# main.net
KiCad netlist of a schematic drawn in Altium Designer
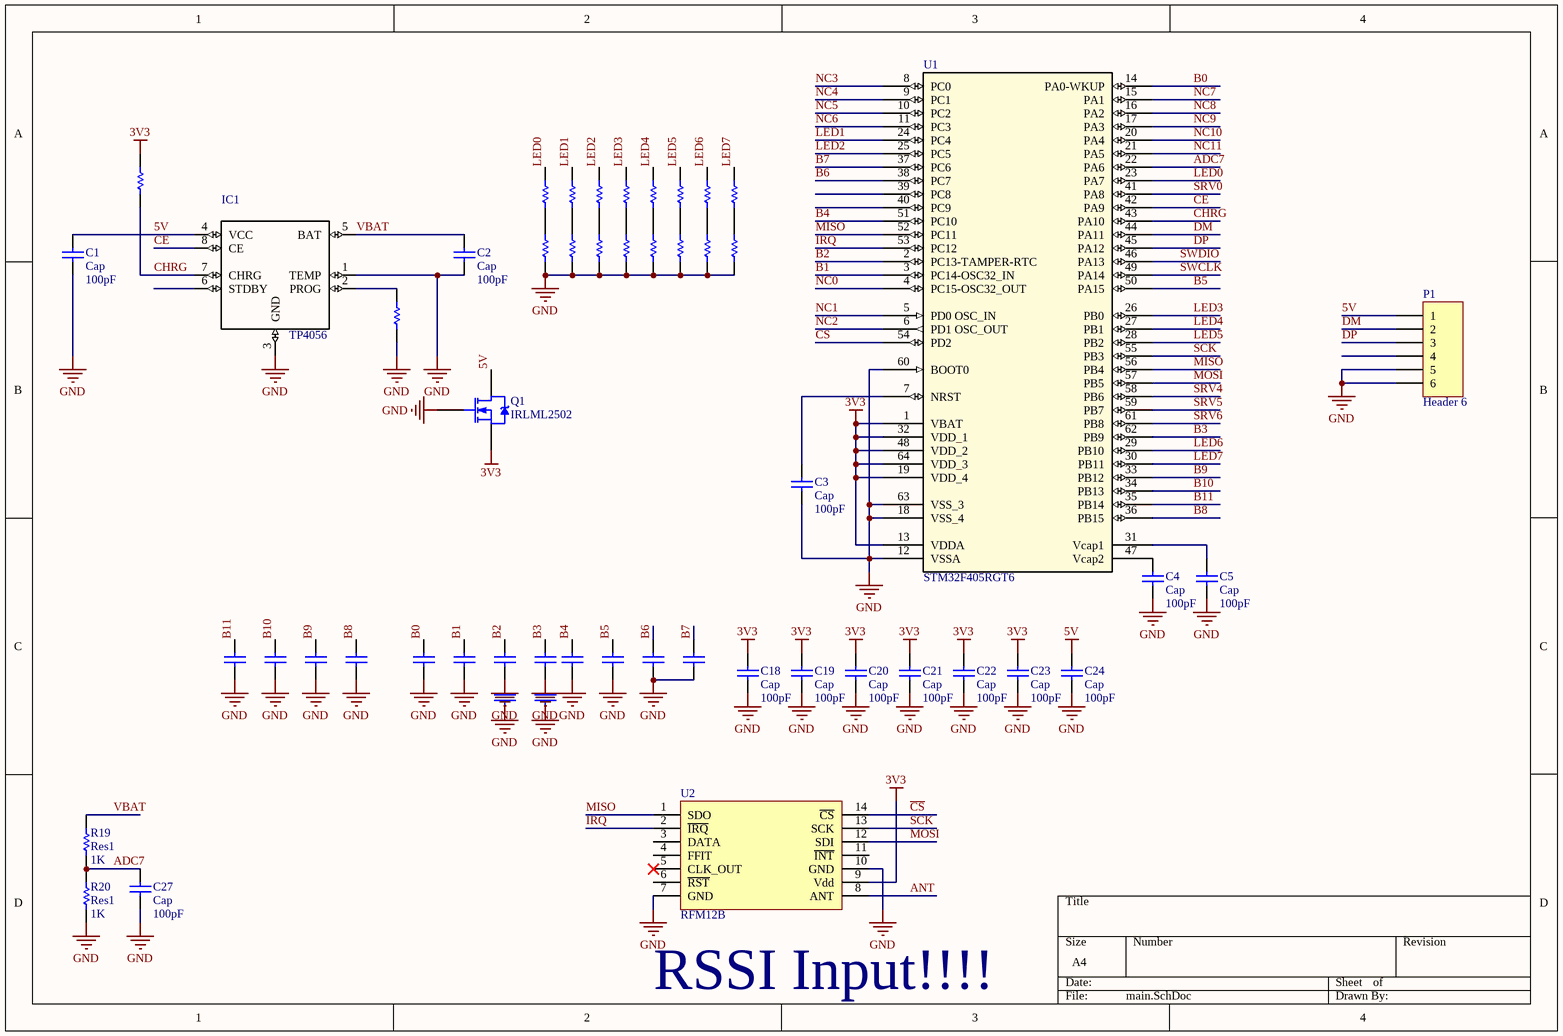
[diagram p0: main.SchDoc]

(export (version "E")
  (design (tool "Eeschema 10.0.6"))
  (components
    (comp (ref "C1")
      (value "Cap")
      (footprint "RC_1210_T1.8")
      (description "Capacitor")
      (fields (field (name "ALTIUM_VALUE") "100pF") (field (name "PUBLISHER") "Altium Limited"))
      (libsource (lib "Miscellaneous Devices") (part "Cap"))
    )
    (comp (ref "C2")
      (value "Cap")
      (footprint "RC_1210_T1.8")
      (description "Capacitor")
      (fields (field (name "ALTIUM_VALUE") "100pF") (field (name "PUBLISHER") "Altium Limited"))
      (libsource (lib "Miscellaneous Devices") (part "Cap"))
    )
    (comp (ref "C3")
      (value "Cap")
      (footprint "RC_0603")
      (description "Capacitor")
      (fields (field (name "ALTIUM_VALUE") "100pF") (field (name "PUBLISHER") "Altium Limited"))
      (libsource (lib "Miscellaneous Devices") (part "Cap"))
    )
    (comp (ref "C4")
      (value "Cap")
      (footprint "RC_0603")
      (description "Capacitor")
      (fields (field (name "ALTIUM_VALUE") "100pF") (field (name "PUBLISHER") "Altium Limited"))
      (libsource (lib "Miscellaneous Devices") (part "Cap"))
    )
    (comp (ref "C5")
      (value "Cap")
      (footprint "RC_0603")
      (description "Capacitor")
      (fields (field (name "ALTIUM_VALUE") "100pF") (field (name "PUBLISHER") "Altium Limited"))
      (libsource (lib "Miscellaneous Devices") (part "Cap"))
    )
    (comp (ref "C6")
      (value "Cap")
      (footprint "RC_0603")
      (description "Capacitor")
      (fields (field (name "PUBLISHER") "Altium Limited"))
      (libsource (lib "Miscellaneous Devices") (part "Cap"))
    )
    (comp (ref "C7")
      (value "Cap")
      (footprint "RC_0603")
      (description "Capacitor")
      (fields (field (name "PUBLISHER") "Altium Limited"))
      (libsource (lib "Miscellaneous Devices") (part "Cap"))
    )
    (comp (ref "C8")
      (value "Cap")
      (footprint "RC_0603")
      (description "Capacitor")
      (fields (field (name "PUBLISHER") "Altium Limited"))
      (libsource (lib "Miscellaneous Devices") (part "Cap"))
    )
    (comp (ref "C9")
      (value "Cap")
      (footprint "RC_0603")
      (description "Capacitor")
      (fields (field (name "PUBLISHER") "Altium Limited"))
      (libsource (lib "Miscellaneous Devices") (part "Cap"))
    )
    (comp (ref "C10")
      (value "Cap")
      (footprint "RC_0603")
      (description "Capacitor")
      (fields (field (name "PUBLISHER") "Altium Limited"))
      (libsource (lib "Miscellaneous Devices") (part "Cap"))
    )
    (comp (ref "C11")
      (value "Cap")
      (footprint "RC_0603")
      (description "Capacitor")
      (fields (field (name "PUBLISHER") "Altium Limited"))
      (libsource (lib "Miscellaneous Devices") (part "Cap"))
    )
    (comp (ref "C12")
      (value "Cap")
      (footprint "RC_0603")
      (description "Capacitor")
      (fields (field (name "PUBLISHER") "Altium Limited"))
      (libsource (lib "Miscellaneous Devices") (part "Cap"))
    )
    (comp (ref "C13")
      (value "Cap")
      (footprint "RC_0603")
      (description "Capacitor")
      (fields (field (name "PUBLISHER") "Altium Limited"))
      (libsource (lib "Miscellaneous Devices") (part "Cap"))
    )
    (comp (ref "C14")
      (value "Cap")
      (footprint "RC_0603")
      (description "Capacitor")
      (fields (field (name "PUBLISHER") "Altium Limited"))
      (libsource (lib "Miscellaneous Devices") (part "Cap"))
    )
    (comp (ref "C15")
      (value "Cap")
      (footprint "RC_0603")
      (description "Capacitor")
      (fields (field (name "PUBLISHER") "Altium Limited"))
      (libsource (lib "Miscellaneous Devices") (part "Cap"))
    )
    (comp (ref "C16")
      (value "Cap")
      (footprint "RC_0603")
      (description "Capacitor")
      (fields (field (name "PUBLISHER") "Altium Limited"))
      (libsource (lib "Miscellaneous Devices") (part "Cap"))
    )
    (comp (ref "C17")
      (value "Cap")
      (footprint "RC_0603")
      (description "Capacitor")
      (fields (field (name "PUBLISHER") "Altium Limited"))
      (libsource (lib "Miscellaneous Devices") (part "Cap"))
    )
    (comp (ref "C18")
      (value "Cap")
      (footprint "RC_0603")
      (description "Capacitor")
      (fields (field (name "ALTIUM_VALUE") "100pF") (field (name "PUBLISHER") "Altium Limited"))
      (libsource (lib "Miscellaneous Devices") (part "Cap"))
    )
    (comp (ref "C19")
      (value "Cap")
      (footprint "RC_0603")
      (description "Capacitor")
      (fields (field (name "ALTIUM_VALUE") "100pF") (field (name "PUBLISHER") "Altium Limited"))
      (libsource (lib "Miscellaneous Devices") (part "Cap"))
    )
    (comp (ref "C20")
      (value "Cap")
      (footprint "RC_0603")
      (description "Capacitor")
      (fields (field (name "ALTIUM_VALUE") "100pF") (field (name "PUBLISHER") "Altium Limited"))
      (libsource (lib "Miscellaneous Devices") (part "Cap"))
    )
    (comp (ref "C21")
      (value "Cap")
      (footprint "RC_0603")
      (description "Capacitor")
      (fields (field (name "ALTIUM_VALUE") "100pF") (field (name "PUBLISHER") "Altium Limited"))
      (libsource (lib "Miscellaneous Devices") (part "Cap"))
    )
    (comp (ref "C22")
      (value "Cap")
      (footprint "RC_0603")
      (description "Capacitor")
      (fields (field (name "ALTIUM_VALUE") "100pF") (field (name "PUBLISHER") "Altium Limited"))
      (libsource (lib "Miscellaneous Devices") (part "Cap"))
    )
    (comp (ref "C23")
      (value "Cap")
      (footprint "RC_0603")
      (description "Capacitor")
      (fields (field (name "ALTIUM_VALUE") "100pF") (field (name "PUBLISHER") "Altium Limited"))
      (libsource (lib "Miscellaneous Devices") (part "Cap"))
    )
    (comp (ref "C24")
      (value "Cap")
      (footprint "RC_0603")
      (description "Capacitor")
      (fields (field (name "ALTIUM_VALUE") "100pF") (field (name "PUBLISHER") "Altium Limited"))
      (libsource (lib "Miscellaneous Devices") (part "Cap"))
    )
    (comp (ref "C25")
      (value "Cap")
      (footprint "RC_0603")
      (description "Capacitor")
      (fields (field (name "PUBLISHER") "Altium Limited"))
      (libsource (lib "Miscellaneous Devices") (part "Cap"))
    )
    (comp (ref "C26")
      (value "Cap")
      (footprint "RC_0603")
      (description "Capacitor")
      (fields (field (name "PUBLISHER") "Altium Limited"))
      (libsource (lib "Miscellaneous Devices") (part "Cap"))
    )
    (comp (ref "C27")
      (value "Cap")
      (footprint "RC_0603")
      (description "Capacitor")
      (fields (field (name "ALTIUM_VALUE") "100pF") (field (name "PUBLISHER") "Altium Limited"))
      (libsource (lib "Miscellaneous Devices") (part "Cap"))
    )
    (comp (ref "IC1")
      (value "TP4056")
      (footprint "*SOP-8")
      (fields (field (name "MF") "NanJing Top Power ASIC Corp."))
      (libsource (lib "TP4056") (part "TP4056"))
    )
    (comp (ref "P1")
      (value "Header 6")
      (footprint "RR_USB_MICRO_#1")
      (description "Header, 6-Pin")
      (fields (field (name "PUBLISHER") "Altium Limited"))
      (libsource (lib "Miscellaneous Connectors") (part "Header 6"))
    )
    (comp (ref "Q1")
      (value "IRLML2502")
      (footprint "RR_SOT-23")
      (description "MOSFET N-CH 20V 4.2A SOT-23-3")
      (fields (field (name "MANUFACTURER") "Infineon Technologies"))
      (libsource (lib "RozumLibrary") (part "IRLML2502"))
    )
    (comp (ref "R1")
      (value "Res1")
      (footprint "RR_0603")
      (description "Resistor")
      (fields (field (name "PUBLISHER") "Altium Limited"))
      (libsource (lib "Miscellaneous Devices") (part "Res1"))
    )
    (comp (ref "R2")
      (value "Res1")
      (footprint "RR_0603")
      (description "Resistor")
      (fields (field (name "PUBLISHER") "Altium Limited"))
      (libsource (lib "Miscellaneous Devices") (part "Res1"))
    )
    (comp (ref "R3")
      (value "Res1")
      (footprint "RR_0603")
      (description "Resistor")
      (fields (field (name "PUBLISHER") "Altium Limited"))
      (libsource (lib "Miscellaneous Devices") (part "Res1"))
    )
    (comp (ref "R4")
      (value "Res1")
      (footprint "RR_0603")
      (description "Resistor")
      (fields (field (name "PUBLISHER") "Altium Limited"))
      (libsource (lib "Miscellaneous Devices") (part "Res1"))
    )
    (comp (ref "R5")
      (value "Res1")
      (footprint "RR_0603")
      (description "Resistor")
      (fields (field (name "PUBLISHER") "Altium Limited"))
      (libsource (lib "Miscellaneous Devices") (part "Res1"))
    )
    (comp (ref "R6")
      (value "Res1")
      (footprint "RR_0603")
      (description "Resistor")
      (fields (field (name "PUBLISHER") "Altium Limited"))
      (libsource (lib "Miscellaneous Devices") (part "Res1"))
    )
    (comp (ref "R7")
      (value "Res1")
      (footprint "RR_0603")
      (description "Resistor")
      (fields (field (name "PUBLISHER") "Altium Limited"))
      (libsource (lib "Miscellaneous Devices") (part "Res1"))
    )
    (comp (ref "R8")
      (value "Res1")
      (footprint "RR_0603")
      (description "Resistor")
      (fields (field (name "PUBLISHER") "Altium Limited"))
      (libsource (lib "Miscellaneous Devices") (part "Res1"))
    )
    (comp (ref "R9")
      (value "Res1")
      (footprint "RR_0603")
      (description "Resistor")
      (fields (field (name "PUBLISHER") "Altium Limited"))
      (libsource (lib "Miscellaneous Devices") (part "Res1"))
    )
    (comp (ref "R10")
      (value "Res1")
      (footprint "RR_0603")
      (description "Resistor")
      (fields (field (name "PUBLISHER") "Altium Limited"))
      (libsource (lib "Miscellaneous Devices") (part "Res1"))
    )
    (comp (ref "R11")
      (value "Res1")
      (footprint "RR_0603")
      (description "Resistor")
      (fields (field (name "PUBLISHER") "Altium Limited"))
      (libsource (lib "Miscellaneous Devices") (part "Res1"))
    )
    (comp (ref "R12")
      (value "Res1")
      (footprint "RR_0603")
      (description "Resistor")
      (fields (field (name "PUBLISHER") "Altium Limited"))
      (libsource (lib "Miscellaneous Devices") (part "Res1"))
    )
    (comp (ref "R13")
      (value "Res1")
      (footprint "RR_0603")
      (description "Resistor")
      (fields (field (name "PUBLISHER") "Altium Limited"))
      (libsource (lib "Miscellaneous Devices") (part "Res1"))
    )
    (comp (ref "R14")
      (value "Res1")
      (footprint "RR_0603")
      (description "Resistor")
      (fields (field (name "PUBLISHER") "Altium Limited"))
      (libsource (lib "Miscellaneous Devices") (part "Res1"))
    )
    (comp (ref "R15")
      (value "Res1")
      (footprint "RR_0603")
      (description "Resistor")
      (fields (field (name "PUBLISHER") "Altium Limited"))
      (libsource (lib "Miscellaneous Devices") (part "Res1"))
    )
    (comp (ref "R16")
      (value "Res1")
      (footprint "RR_0603")
      (description "Resistor")
      (fields (field (name "PUBLISHER") "Altium Limited"))
      (libsource (lib "Miscellaneous Devices") (part "Res1"))
    )
    (comp (ref "R17")
      (value "Res1")
      (footprint "RR_0603")
      (description "Resistor")
      (fields (field (name "PUBLISHER") "Altium Limited"))
      (libsource (lib "Miscellaneous Devices") (part "Res1"))
    )
    (comp (ref "R18")
      (value "Res1")
      (footprint "RR_0603")
      (description "Resistor")
      (fields (field (name "PUBLISHER") "Altium Limited"))
      (libsource (lib "Miscellaneous Devices") (part "Res1"))
    )
    (comp (ref "R19")
      (value "Res1")
      (footprint "RR_0603")
      (description "Resistor")
      (fields (field (name "ALTIUM_VALUE") "1K") (field (name "PUBLISHER") "Altium Limited"))
      (libsource (lib "Miscellaneous Devices") (part "Res1"))
    )
    (comp (ref "R20")
      (value "Res1")
      (footprint "RR_0603")
      (description "Resistor")
      (fields (field (name "ALTIUM_VALUE") "1K") (field (name "PUBLISHER") "Altium Limited"))
      (libsource (lib "Miscellaneous Devices") (part "Res1"))
    )
    (comp (ref "U1")
      (value "STM32F405RGT6")
      (footprint "RR_LQFP-64")
      (description "MCU STM32F405RGT6")
      (fields (field (name "MANUFACTURER") "ST Microelectronics"))
      (libsource (lib "RozumLibrary") (part "STM32F405RGT6"))
    )
    (comp (ref "U2") (value "RFM12B") (libsource (lib "Schlib1") (part "Component_1")))
  )
  (nets
    (net (code "1") (name "/ADC7") (class "Default")
      (node (ref "C27") (pin "2") (pinfunction "2_2") (pintype "passive"))
      (node (ref "R19") (pin "1") (pinfunction "1_1") (pintype "passive"))
      (node (ref "R20") (pin "2") (pinfunction "2_2") (pintype "passive"))
      (node (ref "U1") (pin "22") (pinfunction "PA6_22") (pintype "bidirectional"))
    )
    (net (code "2") (name "/ANT") (class "Default")
      (node (ref "U2") (pin "8") (pinfunction "ANT_8") (pintype "passive"))
    )
    (net (code "3") (name "/B0") (class "Default")
      (node (ref "C10") (pin "2") (pinfunction "2_2") (pintype "passive"))
      (node (ref "U1") (pin "14") (pinfunction "PA0-WKUP_14") (pintype "bidirectional"))
    )
    (net (code "4") (name "/B1") (class "Default")
      (node (ref "C11") (pin "2") (pinfunction "2_2") (pintype "passive"))
      (node (ref "U1") (pin "3") (pinfunction "PC14-OSC32_IN_3") (pintype "bidirectional"))
    )
    (net (code "5") (name "/B2") (class "Default")
      (node (ref "C12") (pin "2") (pinfunction "2_2") (pintype "passive"))
      (node (ref "U1") (pin "2") (pinfunction "PC13-TAMPER-RTC_2") (pintype "bidirectional"))
    )
    (net (code "6") (name "/B3") (class "Default")
      (node (ref "C13") (pin "2") (pinfunction "2_2") (pintype "passive"))
      (node (ref "U1") (pin "62") (pinfunction "PB9_62") (pintype "bidirectional"))
    )
    (net (code "7") (name "/B4") (class "Default")
      (node (ref "C14") (pin "2") (pinfunction "2_2") (pintype "passive"))
      (node (ref "U1") (pin "51") (pinfunction "PC10_51") (pintype "bidirectional"))
    )
    (net (code "8") (name "/B5") (class "Default")
      (node (ref "C15") (pin "2") (pinfunction "2_2") (pintype "passive"))
      (node (ref "U1") (pin "50") (pinfunction "PA15_50") (pintype "bidirectional"))
    )
    (net (code "9") (name "/B6") (class "Default")
      (node (ref "C16") (pin "2") (pinfunction "2_2") (pintype "passive"))
      (node (ref "U1") (pin "38") (pinfunction "PC7_38") (pintype "bidirectional"))
    )
    (net (code "10") (name "/B7") (class "Default")
      (node (ref "C17") (pin "2") (pinfunction "2_2") (pintype "passive"))
      (node (ref "U1") (pin "37") (pinfunction "PC6_37") (pintype "bidirectional"))
    )
    (net (code "11") (name "/B8") (class "Default")
      (node (ref "C9") (pin "2") (pinfunction "2_2") (pintype "passive"))
      (node (ref "U1") (pin "36") (pinfunction "PB15_36") (pintype "bidirectional"))
    )
    (net (code "12") (name "/B9") (class "Default")
      (node (ref "C8") (pin "2") (pinfunction "2_2") (pintype "passive"))
      (node (ref "U1") (pin "33") (pinfunction "PB12_33") (pintype "bidirectional"))
    )
    (net (code "13") (name "/B10") (class "Default")
      (node (ref "C7") (pin "2") (pinfunction "2_2") (pintype "passive"))
      (node (ref "U1") (pin "34") (pinfunction "PB13_34") (pintype "bidirectional"))
    )
    (net (code "14") (name "/B11") (class "Default")
      (node (ref "C6") (pin "2") (pinfunction "2_2") (pintype "passive"))
      (node (ref "U1") (pin "35") (pinfunction "PB14_35") (pintype "bidirectional"))
    )
    (net (code "15") (name "/CE") (class "Default")
      (node (ref "IC1") (pin "8") (pinfunction "CE_8") (pintype "bidirectional"))
      (node (ref "U1") (pin "42") (pinfunction "PA9_42") (pintype "bidirectional"))
    )
    (net (code "16") (name "/CHRG") (class "Default")
      (node (ref "IC1") (pin "7") (pinfunction "CHRG_7") (pintype "bidirectional"))
      (node (ref "R1") (pin "1") (pinfunction "1_1") (pintype "passive"))
      (node (ref "U1") (pin "43") (pinfunction "PA10_43") (pintype "bidirectional"))
    )
    (net (code "17") (name "/DM") (class "Default")
      (node (ref "P1") (pin "2") (pinfunction "2_2") (pintype "passive"))
      (node (ref "U1") (pin "44") (pinfunction "PA11_44") (pintype "bidirectional"))
    )
    (net (code "18") (name "/DP") (class "Default")
      (node (ref "P1") (pin "3") (pinfunction "3_3") (pintype "passive"))
      (node (ref "U1") (pin "45") (pinfunction "PA12_45") (pintype "bidirectional"))
    )
    (net (code "19") (name "/LED0") (class "Default")
      (node (ref "R2") (pin "2") (pinfunction "2_2") (pintype "passive"))
      (node (ref "U1") (pin "23") (pinfunction "PA7_23") (pintype "bidirectional"))
    )
    (net (code "20") (name "/LED1") (class "Default")
      (node (ref "R3") (pin "2") (pinfunction "2_2") (pintype "passive"))
      (node (ref "U1") (pin "24") (pinfunction "PC4_24") (pintype "bidirectional"))
    )
    (net (code "21") (name "/LED2") (class "Default")
      (node (ref "R4") (pin "2") (pinfunction "2_2") (pintype "passive"))
      (node (ref "U1") (pin "25") (pinfunction "PC5_25") (pintype "bidirectional"))
    )
    (net (code "22") (name "/LED3") (class "Default")
      (node (ref "R5") (pin "2") (pinfunction "2_2") (pintype "passive"))
      (node (ref "U1") (pin "26") (pinfunction "PB0_26") (pintype "bidirectional"))
    )
    (net (code "23") (name "/LED4") (class "Default")
      (node (ref "R6") (pin "2") (pinfunction "2_2") (pintype "passive"))
      (node (ref "U1") (pin "27") (pinfunction "PB1_27") (pintype "bidirectional"))
    )
    (net (code "24") (name "/LED5") (class "Default")
      (node (ref "R7") (pin "2") (pinfunction "2_2") (pintype "passive"))
      (node (ref "U1") (pin "28") (pinfunction "PB2_28") (pintype "bidirectional"))
    )
    (net (code "25") (name "/LED6") (class "Default")
      (node (ref "R8") (pin "2") (pinfunction "2_2") (pintype "passive"))
      (node (ref "U1") (pin "29") (pinfunction "PB10_29") (pintype "bidirectional"))
    )
    (net (code "26") (name "/LED7") (class "Default")
      (node (ref "R9") (pin "2") (pinfunction "2_2") (pintype "passive"))
      (node (ref "U1") (pin "30") (pinfunction "PB11_30") (pintype "bidirectional"))
    )
    (net (code "27") (name "/MISO") (class "Default")
      (node (ref "U1") (pin "52") (pinfunction "PC11_52") (pintype "bidirectional"))
      (node (ref "U1") (pin "56") (pinfunction "PB4_56") (pintype "bidirectional"))
      (node (ref "U2") (pin "1") (pinfunction "SDO_1") (pintype "passive"))
    )
    (net (code "28") (name "/MOSI") (class "Default")
      (node (ref "U1") (pin "57") (pinfunction "PB5_57") (pintype "bidirectional"))
      (node (ref "U2") (pin "12") (pinfunction "SDI_12") (pintype "passive"))
    )
    (net (code "29") (name "/NC0") (class "Default")
      (node (ref "U1") (pin "4") (pinfunction "PC15-OSC32_OUT_4") (pintype "bidirectional"))
    )
    (net (code "30") (name "/NC1") (class "Default")
      (node (ref "U1") (pin "5") (pinfunction "PD0_OSC_IN_5") (pintype "input"))
    )
    (net (code "31") (name "/NC2") (class "Default")
      (node (ref "U1") (pin "6") (pinfunction "PD1_OSC_OUT_6") (pintype "output"))
    )
    (net (code "32") (name "/NC3") (class "Default")
      (node (ref "U1") (pin "8") (pinfunction "PC0_8") (pintype "bidirectional"))
    )
    (net (code "33") (name "/NC4") (class "Default")
      (node (ref "U1") (pin "9") (pinfunction "PC1_9") (pintype "bidirectional"))
    )
    (net (code "34") (name "/NC5") (class "Default")
      (node (ref "U1") (pin "10") (pinfunction "PC2_10") (pintype "bidirectional"))
    )
    (net (code "35") (name "/NC6") (class "Default")
      (node (ref "U1") (pin "11") (pinfunction "PC3_11") (pintype "bidirectional"))
    )
    (net (code "36") (name "/NC7") (class "Default")
      (node (ref "U1") (pin "15") (pinfunction "PA1_15") (pintype "bidirectional"))
    )
    (net (code "37") (name "/NC8") (class "Default")
      (node (ref "U1") (pin "16") (pinfunction "PA2_16") (pintype "bidirectional"))
    )
    (net (code "38") (name "/NC9") (class "Default")
      (node (ref "U1") (pin "17") (pinfunction "PA3_17") (pintype "bidirectional"))
    )
    (net (code "39") (name "/NC10") (class "Default")
      (node (ref "U1") (pin "20") (pinfunction "PA4_20") (pintype "bidirectional"))
    )
    (net (code "40") (name "/NC11") (class "Default")
      (node (ref "U1") (pin "21") (pinfunction "PA5_21") (pintype "bidirectional"))
    )
    (net (code "41") (name "/SCK") (class "Default")
      (node (ref "U1") (pin "55") (pinfunction "PB3_55") (pintype "bidirectional"))
      (node (ref "U2") (pin "13") (pinfunction "SCK_13") (pintype "passive"))
    )
    (net (code "42") (name "/SRV0") (class "Default")
      (node (ref "U1") (pin "41") (pinfunction "PA8_41") (pintype "bidirectional"))
    )
    (net (code "43") (name "/SRV4") (class "Default")
      (node (ref "U1") (pin "58") (pinfunction "PB6_58") (pintype "bidirectional"))
    )
    (net (code "44") (name "/SRV5") (class "Default")
      (node (ref "U1") (pin "59") (pinfunction "PB7_59") (pintype "bidirectional"))
    )
    (net (code "45") (name "/SRV6") (class "Default")
      (node (ref "U1") (pin "61") (pinfunction "PB8_61") (pintype "bidirectional"))
    )
    (net (code "46") (name "/SWCLK") (class "Default")
      (node (ref "U1") (pin "49") (pinfunction "PA14_49") (pintype "bidirectional"))
    )
    (net (code "47") (name "/SWDIO") (class "Default")
      (node (ref "U1") (pin "46") (pinfunction "PA13_46") (pintype "bidirectional"))
    )
    (net (code "48") (name "/VBAT") (class "Default")
      (node (ref "C2") (pin "2") (pinfunction "2_2") (pintype "passive"))
      (node (ref "IC1") (pin "5") (pinfunction "BAT_5") (pintype "bidirectional"))
      (node (ref "R19") (pin "2") (pinfunction "2_2") (pintype "passive"))
    )
    (net (code "49") (name "/~{CS}") (class "Default")
      (node (ref "U1") (pin "54") (pinfunction "PD2_54") (pintype "bidirectional"))
      (node (ref "U2") (pin "14") (pinfunction "~{CS}_14") (pintype "passive"))
    )
    (net (code "50") (name "/~{IRQ}") (class "Default")
      (node (ref "U1") (pin "53") (pinfunction "PC12_53") (pintype "bidirectional"))
      (node (ref "U2") (pin "2") (pinfunction "~{IRQ}_2") (pintype "passive"))
    )
    (net (code "51") (name "3V3") (class "Default")
      (node (ref "C18") (pin "2") (pinfunction "2_2") (pintype "passive"))
      (node (ref "C19") (pin "2") (pinfunction "2_2") (pintype "passive"))
      (node (ref "C20") (pin "2") (pinfunction "2_2") (pintype "passive"))
      (node (ref "C21") (pin "2") (pinfunction "2_2") (pintype "passive"))
      (node (ref "C22") (pin "2") (pinfunction "2_2") (pintype "passive"))
      (node (ref "C23") (pin "2") (pinfunction "2_2") (pintype "passive"))
      (node (ref "Q1") (pin "2") (pinfunction "S_2") (pintype "passive"))
      (node (ref "R1") (pin "2") (pinfunction "2_2") (pintype "passive"))
      (node (ref "U1") (pin "1") (pinfunction "VBAT_1") (pintype "power_in"))
      (node (ref "U1") (pin "13") (pinfunction "VDDA_13") (pintype "power_in"))
      (node (ref "U1") (pin "19") (pinfunction "VDD_4_19") (pintype "power_in"))
      (node (ref "U1") (pin "32") (pinfunction "VDD_1_32") (pintype "power_in"))
      (node (ref "U1") (pin "48") (pinfunction "VDD_2_48") (pintype "power_in"))
      (node (ref "U1") (pin "64") (pinfunction "VDD_3_64") (pintype "power_in"))
      (node (ref "U2") (pin "9") (pinfunction "Vdd_9") (pintype "passive"))
    )
    (net (code "52") (name "5V") (class "Default")
      (node (ref "C1") (pin "2") (pinfunction "2_2") (pintype "passive"))
      (node (ref "C24") (pin "2") (pinfunction "2_2") (pintype "passive"))
      (node (ref "IC1") (pin "4") (pinfunction "VCC_4") (pintype "bidirectional"))
      (node (ref "P1") (pin "1") (pinfunction "1_1") (pintype "passive"))
      (node (ref "Q1") (pin "3") (pinfunction "D_3") (pintype "passive"))
    )
    (net (code "53") (name "GND") (class "Default")
      (node (ref "C1") (pin "1") (pinfunction "1_1") (pintype "passive"))
      (node (ref "C10") (pin "1") (pinfunction "1_1") (pintype "passive"))
      (node (ref "C11") (pin "1") (pinfunction "1_1") (pintype "passive"))
      (node (ref "C12") (pin "1") (pinfunction "1_1") (pintype "passive"))
      (node (ref "C13") (pin "1") (pinfunction "1_1") (pintype "passive"))
      (node (ref "C14") (pin "1") (pinfunction "1_1") (pintype "passive"))
      (node (ref "C15") (pin "1") (pinfunction "1_1") (pintype "passive"))
      (node (ref "C16") (pin "1") (pinfunction "1_1") (pintype "passive"))
      (node (ref "C17") (pin "1") (pinfunction "1_1") (pintype "passive"))
      (node (ref "C18") (pin "1") (pinfunction "1_1") (pintype "passive"))
      (node (ref "C19") (pin "1") (pinfunction "1_1") (pintype "passive"))
      (node (ref "C2") (pin "1") (pinfunction "1_1") (pintype "passive"))
      (node (ref "C20") (pin "1") (pinfunction "1_1") (pintype "passive"))
      (node (ref "C21") (pin "1") (pinfunction "1_1") (pintype "passive"))
      (node (ref "C22") (pin "1") (pinfunction "1_1") (pintype "passive"))
      (node (ref "C23") (pin "1") (pinfunction "1_1") (pintype "passive"))
      (node (ref "C24") (pin "1") (pinfunction "1_1") (pintype "passive"))
      (node (ref "C27") (pin "1") (pinfunction "1_1") (pintype "passive"))
      (node (ref "C3") (pin "1") (pinfunction "1_1") (pintype "passive"))
      (node (ref "C4") (pin "1") (pinfunction "1_1") (pintype "passive"))
      (node (ref "C5") (pin "1") (pinfunction "1_1") (pintype "passive"))
      (node (ref "C6") (pin "1") (pinfunction "1_1") (pintype "passive"))
      (node (ref "C7") (pin "1") (pinfunction "1_1") (pintype "passive"))
      (node (ref "C8") (pin "1") (pinfunction "1_1") (pintype "passive"))
      (node (ref "C9") (pin "1") (pinfunction "1_1") (pintype "passive"))
      (node (ref "IC1") (pin "1") (pinfunction "TEMP_1") (pintype "bidirectional"))
      (node (ref "IC1") (pin "3") (pinfunction "GND_3") (pintype "bidirectional"))
      (node (ref "P1") (pin "5") (pinfunction "5_5") (pintype "passive"))
      (node (ref "P1") (pin "6") (pinfunction "6_6") (pintype "passive"))
      (node (ref "Q1") (pin "1") (pinfunction "G_1") (pintype "passive"))
      (node (ref "R10") (pin "1") (pinfunction "1_1") (pintype "passive"))
      (node (ref "R11") (pin "1") (pinfunction "1_1") (pintype "passive"))
      (node (ref "R12") (pin "1") (pinfunction "1_1") (pintype "passive"))
      (node (ref "R13") (pin "1") (pinfunction "1_1") (pintype "passive"))
      (node (ref "R14") (pin "1") (pinfunction "1_1") (pintype "passive"))
      (node (ref "R15") (pin "1") (pinfunction "1_1") (pintype "passive"))
      (node (ref "R16") (pin "1") (pinfunction "1_1") (pintype "passive"))
      (node (ref "R17") (pin "1") (pinfunction "1_1") (pintype "passive"))
      (node (ref "R18") (pin "1") (pinfunction "1_1") (pintype "passive"))
      (node (ref "R20") (pin "1") (pinfunction "1_1") (pintype "passive"))
      (node (ref "U1") (pin "12") (pinfunction "VSSA_12") (pintype "power_in"))
      (node (ref "U1") (pin "18") (pinfunction "VSS_4_18") (pintype "power_in"))
      (node (ref "U1") (pin "60") (pinfunction "BOOT0_60") (pintype "input"))
      (node (ref "U1") (pin "63") (pinfunction "VSS_3_63") (pintype "power_in"))
      (node (ref "U2") (pin "10") (pinfunction "GND_10") (pintype "passive"))
      (node (ref "U2") (pin "7") (pinfunction "GND_7") (pintype "passive"))
    )
    (net (code "54") (name "Net-(IC1-PROG)") (class "Default")
      (node (ref "IC1") (pin "2") (pinfunction "PROG_2") (pintype "bidirectional"))
      (node (ref "R18") (pin "2") (pinfunction "2_2") (pintype "passive"))
    )
    (net (code "55") (name "Net-(R10-Pad2)") (class "Default")
      (node (ref "R10") (pin "2") (pinfunction "2_2") (pintype "passive"))
      (node (ref "R2") (pin "1") (pinfunction "1_1") (pintype "passive"))
    )
    (net (code "56") (name "Net-(R11-Pad2)") (class "Default")
      (node (ref "R11") (pin "2") (pinfunction "2_2") (pintype "passive"))
      (node (ref "R3") (pin "1") (pinfunction "1_1") (pintype "passive"))
    )
    (net (code "57") (name "Net-(R12-Pad2)") (class "Default")
      (node (ref "R12") (pin "2") (pinfunction "2_2") (pintype "passive"))
      (node (ref "R4") (pin "1") (pinfunction "1_1") (pintype "passive"))
    )
    (net (code "58") (name "Net-(R13-Pad2)") (class "Default")
      (node (ref "R13") (pin "2") (pinfunction "2_2") (pintype "passive"))
      (node (ref "R5") (pin "1") (pinfunction "1_1") (pintype "passive"))
    )
    (net (code "59") (name "Net-(R14-Pad2)") (class "Default")
      (node (ref "R14") (pin "2") (pinfunction "2_2") (pintype "passive"))
      (node (ref "R6") (pin "1") (pinfunction "1_1") (pintype "passive"))
    )
    (net (code "60") (name "Net-(R15-Pad2)") (class "Default")
      (node (ref "R15") (pin "2") (pinfunction "2_2") (pintype "passive"))
      (node (ref "R7") (pin "1") (pinfunction "1_1") (pintype "passive"))
    )
    (net (code "61") (name "Net-(R16-Pad2)") (class "Default")
      (node (ref "R16") (pin "2") (pinfunction "2_2") (pintype "passive"))
      (node (ref "R8") (pin "1") (pinfunction "1_1") (pintype "passive"))
    )
    (net (code "62") (name "Net-(R17-Pad2)") (class "Default")
      (node (ref "R17") (pin "2") (pinfunction "2_2") (pintype "passive"))
      (node (ref "R9") (pin "1") (pinfunction "1_1") (pintype "passive"))
    )
    (net (code "63") (name "Net-(U1-NRST)") (class "Default")
      (node (ref "C3") (pin "2") (pinfunction "2_2") (pintype "passive"))
      (node (ref "U1") (pin "7") (pinfunction "NRST_7") (pintype "bidirectional"))
    )
    (net (code "64") (name "Net-(U1-Vcap1)") (class "Default")
      (node (ref "C5") (pin "2") (pinfunction "2_2") (pintype "passive"))
      (node (ref "U1") (pin "31") (pinfunction "Vcap1_31") (pintype "power_in"))
    )
    (net (code "65") (name "Net-(U1-Vcap2)") (class "Default")
      (node (ref "C4") (pin "2") (pinfunction "2_2") (pintype "passive"))
      (node (ref "U1") (pin "47") (pinfunction "Vcap2_47") (pintype "power_in"))
    )
    (net (code "66") (name "unconnected-(C25-Pad1)") (class "Default")
      (node (ref "C25") (pin "1") (pinfunction "1_1") (pintype "passive"))
    )
    (net (code "67") (name "unconnected-(C25-Pad2)") (class "Default")
      (node (ref "C25") (pin "2") (pinfunction "2_2") (pintype "passive"))
    )
    (net (code "68") (name "unconnected-(C26-Pad1)") (class "Default")
      (node (ref "C26") (pin "1") (pinfunction "1_1") (pintype "passive"))
    )
    (net (code "69") (name "unconnected-(C26-Pad2)") (class "Default")
      (node (ref "C26") (pin "2") (pinfunction "2_2") (pintype "passive"))
    )
    (net (code "70") (name "unconnected-(IC1-STDBY-Pad6)") (class "Default")
      (node (ref "IC1") (pin "6") (pinfunction "STDBY_6") (pintype "bidirectional"))
    )
    (net (code "71") (name "unconnected-(P1-Pad4)") (class "Default")
      (node (ref "P1") (pin "4") (pinfunction "4_4") (pintype "passive"))
    )
    (net (code "72") (name "unconnected-(U1-PC8-Pad39)") (class "Default")
      (node (ref "U1") (pin "39") (pinfunction "PC8_39") (pintype "bidirectional"))
    )
    (net (code "73") (name "unconnected-(U1-PC9-Pad40)") (class "Default")
      (node (ref "U1") (pin "40") (pinfunction "PC9_40") (pintype "bidirectional"))
    )
    (net (code "74") (name "unconnected-(U2-CLK_OUT-Pad5)") (class "Default")
      (node (ref "U2") (pin "5") (pinfunction "CLK_OUT_5") (pintype "passive+no_connect"))
    )
    (net (code "75") (name "unconnected-(U2-DATA-Pad3)") (class "Default")
      (node (ref "U2") (pin "3") (pinfunction "DATA_3") (pintype "passive"))
    )
    (net (code "76") (name "unconnected-(U2-FFIT-Pad4)") (class "Default")
      (node (ref "U2") (pin "4") (pinfunction "FFIT_4") (pintype "passive"))
    )
    (net (code "77") (name "unconnected-(U2-~{INT}-Pad11)") (class "Default")
      (node (ref "U2") (pin "11") (pinfunction "~{INT}_11") (pintype "passive"))
    )
    (net (code "78") (name "unconnected-(U2-~{RST}-Pad6)") (class "Default")
      (node (ref "U2") (pin "6") (pinfunction "~{RST}_6") (pintype "passive"))
    )
  )
)
